# Pin_Expansion.net
KiCad netlist of a schematic drawn in Altium Designer
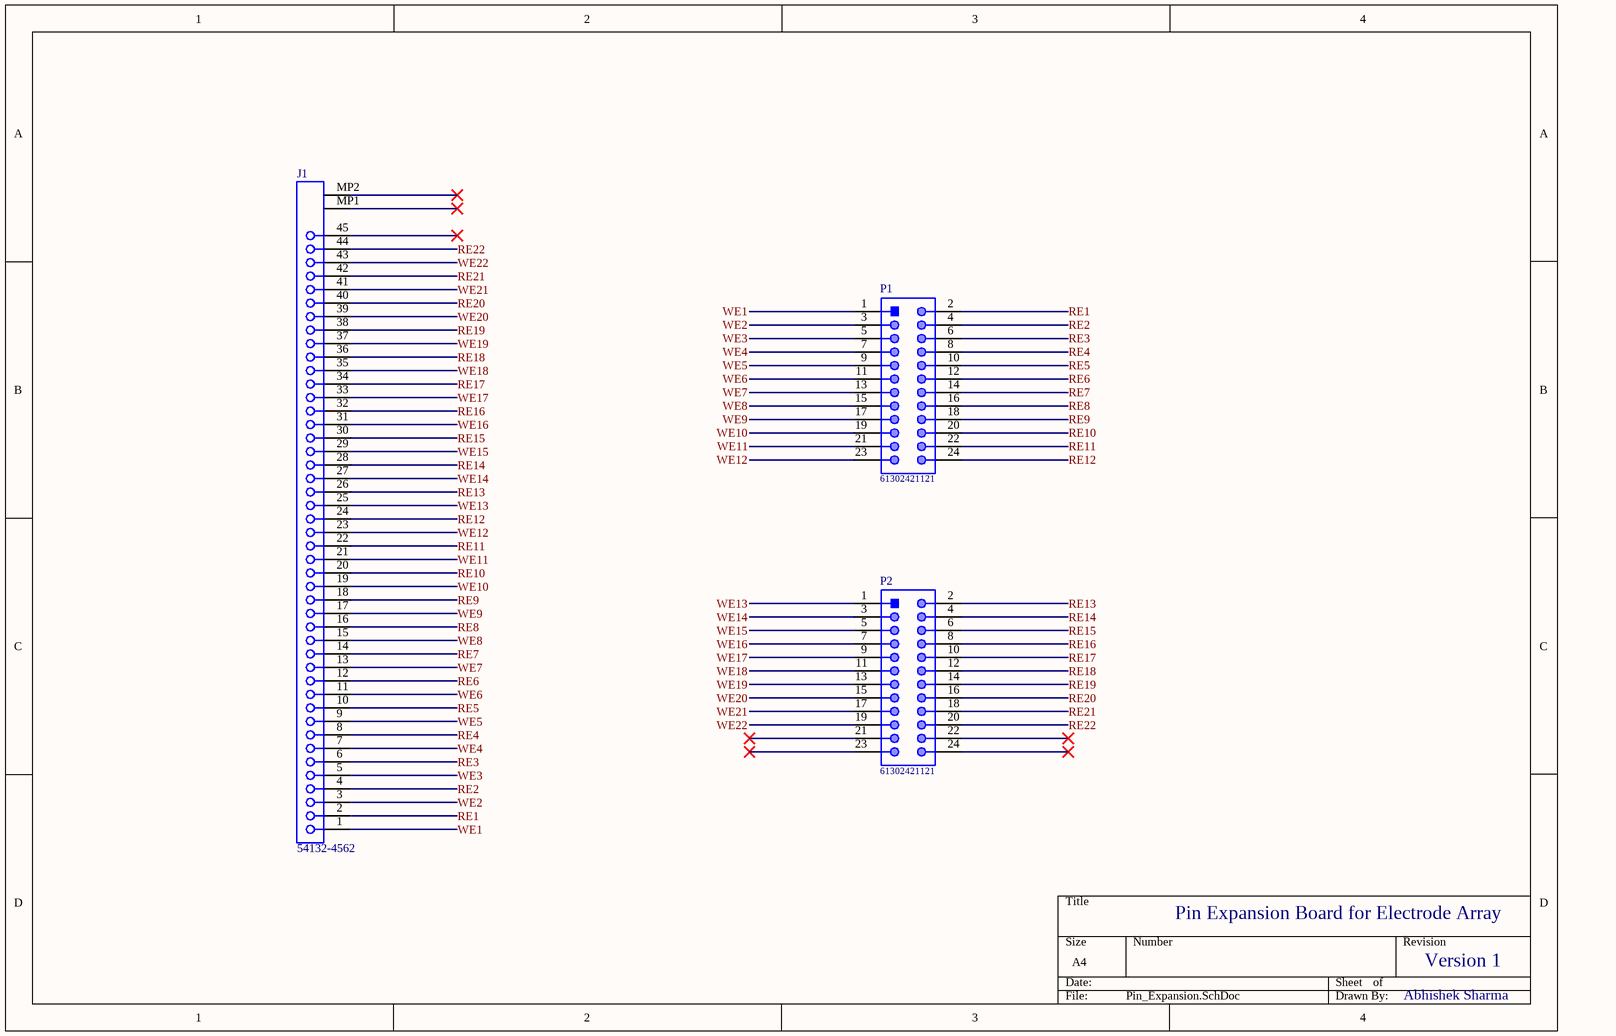
[diagram p0: Pin_Expansion.SchDoc]

(export (version "E")
  (design (tool "Eeschema 10.0.6"))
  (components
    (comp (ref "J1")
      (value "54132-4562")
      (footprint "MOLX-54132-4562")
      (fields (field (name "MANUFACTURER") "Molex"))
      (libsource (lib "Altium Content Vault") (part "MOLX-54132-4562"))
    )
    (comp (ref "P1")
      (value "61302421121")
      (footprint "61302421121")
      (description "THT Vertical Pin Header WR-PHD, Pitch 2.54 mm, Dual Row, 24 pins")
      (fields (field (name "MANUFACTURER") "Wurth Elektronik") (field (name "PUBLISHER") "WurthElektronik"))
      (libsource (lib "Altium Content Vault") (part "WE-CN-2P-M-R24"))
    )
    (comp (ref "P2")
      (value "61302421121")
      (footprint "61302421121")
      (description "THT Vertical Pin Header WR-PHD, Pitch 2.54 mm, Dual Row, 24 pins")
      (fields (field (name "MANUFACTURER") "Wurth Elektronik") (field (name "PUBLISHER") "WurthElektronik"))
      (libsource (lib "Altium Content Vault") (part "WE-CN-2P-M-R24"))
    )
  )
  (nets
    (net (code "1") (name "/RE1") (class "Default")
      (node (ref "J1") (pin "2") (pinfunction "2_2") (pintype "passive"))
      (node (ref "P1") (pin "2") (pinfunction "2_2") (pintype "passive"))
    )
    (net (code "2") (name "/RE2") (class "Default")
      (node (ref "J1") (pin "4") (pinfunction "4_4") (pintype "passive"))
      (node (ref "P1") (pin "4") (pinfunction "4_4") (pintype "passive"))
    )
    (net (code "3") (name "/RE3") (class "Default")
      (node (ref "J1") (pin "6") (pinfunction "6_6") (pintype "passive"))
      (node (ref "P1") (pin "6") (pinfunction "6_6") (pintype "passive"))
    )
    (net (code "4") (name "/RE4") (class "Default")
      (node (ref "J1") (pin "8") (pinfunction "8_8") (pintype "passive"))
      (node (ref "P1") (pin "8") (pinfunction "8_8") (pintype "passive"))
    )
    (net (code "5") (name "/RE5") (class "Default")
      (node (ref "J1") (pin "10") (pinfunction "10_10") (pintype "passive"))
      (node (ref "P1") (pin "10") (pinfunction "10_10") (pintype "passive"))
    )
    (net (code "6") (name "/RE6") (class "Default")
      (node (ref "J1") (pin "12") (pinfunction "12_12") (pintype "passive"))
      (node (ref "P1") (pin "12") (pinfunction "12_12") (pintype "passive"))
    )
    (net (code "7") (name "/RE7") (class "Default")
      (node (ref "J1") (pin "14") (pinfunction "14_14") (pintype "passive"))
      (node (ref "P1") (pin "14") (pinfunction "14_14") (pintype "passive"))
    )
    (net (code "8") (name "/RE8") (class "Default")
      (node (ref "J1") (pin "16") (pinfunction "16_16") (pintype "passive"))
      (node (ref "P1") (pin "16") (pinfunction "16_16") (pintype "passive"))
    )
    (net (code "9") (name "/RE9") (class "Default")
      (node (ref "J1") (pin "18") (pinfunction "18_18") (pintype "passive"))
      (node (ref "P1") (pin "18") (pinfunction "18_18") (pintype "passive"))
    )
    (net (code "10") (name "/RE10") (class "Default")
      (node (ref "J1") (pin "20") (pinfunction "20_20") (pintype "passive"))
      (node (ref "P1") (pin "20") (pinfunction "20_20") (pintype "passive"))
    )
    (net (code "11") (name "/RE11") (class "Default")
      (node (ref "J1") (pin "22") (pinfunction "22_22") (pintype "passive"))
      (node (ref "P1") (pin "22") (pinfunction "22_22") (pintype "passive"))
    )
    (net (code "12") (name "/RE12") (class "Default")
      (node (ref "J1") (pin "24") (pinfunction "24_24") (pintype "passive"))
      (node (ref "P1") (pin "24") (pinfunction "24_24") (pintype "passive"))
    )
    (net (code "13") (name "/RE13") (class "Default")
      (node (ref "J1") (pin "26") (pinfunction "26_26") (pintype "passive"))
      (node (ref "P2") (pin "2") (pinfunction "2_2") (pintype "passive"))
    )
    (net (code "14") (name "/RE14") (class "Default")
      (node (ref "J1") (pin "28") (pinfunction "28_28") (pintype "passive"))
      (node (ref "P2") (pin "4") (pinfunction "4_4") (pintype "passive"))
    )
    (net (code "15") (name "/RE15") (class "Default")
      (node (ref "J1") (pin "30") (pinfunction "30_30") (pintype "passive"))
      (node (ref "P2") (pin "6") (pinfunction "6_6") (pintype "passive"))
    )
    (net (code "16") (name "/RE16") (class "Default")
      (node (ref "J1") (pin "32") (pinfunction "32_32") (pintype "passive"))
      (node (ref "P2") (pin "8") (pinfunction "8_8") (pintype "passive"))
    )
    (net (code "17") (name "/RE17") (class "Default")
      (node (ref "J1") (pin "34") (pinfunction "34_34") (pintype "passive"))
      (node (ref "P2") (pin "10") (pinfunction "10_10") (pintype "passive"))
    )
    (net (code "18") (name "/RE18") (class "Default")
      (node (ref "J1") (pin "36") (pinfunction "36_36") (pintype "passive"))
      (node (ref "P2") (pin "12") (pinfunction "12_12") (pintype "passive"))
    )
    (net (code "19") (name "/RE19") (class "Default")
      (node (ref "J1") (pin "38") (pinfunction "38_38") (pintype "passive"))
      (node (ref "P2") (pin "14") (pinfunction "14_14") (pintype "passive"))
    )
    (net (code "20") (name "/RE20") (class "Default")
      (node (ref "J1") (pin "40") (pinfunction "40_40") (pintype "passive"))
      (node (ref "P2") (pin "16") (pinfunction "16_16") (pintype "passive"))
    )
    (net (code "21") (name "/RE21") (class "Default")
      (node (ref "J1") (pin "42") (pinfunction "42_42") (pintype "passive"))
      (node (ref "P2") (pin "18") (pinfunction "18_18") (pintype "passive"))
    )
    (net (code "22") (name "/RE22") (class "Default")
      (node (ref "J1") (pin "44") (pinfunction "44_44") (pintype "passive"))
      (node (ref "P2") (pin "20") (pinfunction "20_20") (pintype "passive"))
    )
    (net (code "23") (name "/WE1") (class "Default")
      (node (ref "J1") (pin "1") (pinfunction "1_1") (pintype "passive"))
      (node (ref "P1") (pin "1") (pinfunction "1_1") (pintype "passive"))
    )
    (net (code "24") (name "/WE2") (class "Default")
      (node (ref "J1") (pin "3") (pinfunction "3_3") (pintype "passive"))
      (node (ref "P1") (pin "3") (pinfunction "3_3") (pintype "passive"))
    )
    (net (code "25") (name "/WE3") (class "Default")
      (node (ref "J1") (pin "5") (pinfunction "5_5") (pintype "passive"))
      (node (ref "P1") (pin "5") (pinfunction "5_5") (pintype "passive"))
    )
    (net (code "26") (name "/WE4") (class "Default")
      (node (ref "J1") (pin "7") (pinfunction "7_7") (pintype "passive"))
      (node (ref "P1") (pin "7") (pinfunction "7_7") (pintype "passive"))
    )
    (net (code "27") (name "/WE5") (class "Default")
      (node (ref "J1") (pin "9") (pinfunction "9_9") (pintype "passive"))
      (node (ref "P1") (pin "9") (pinfunction "9_9") (pintype "passive"))
    )
    (net (code "28") (name "/WE6") (class "Default")
      (node (ref "J1") (pin "11") (pinfunction "11_11") (pintype "passive"))
      (node (ref "P1") (pin "11") (pinfunction "11_11") (pintype "passive"))
    )
    (net (code "29") (name "/WE7") (class "Default")
      (node (ref "J1") (pin "13") (pinfunction "13_13") (pintype "passive"))
      (node (ref "P1") (pin "13") (pinfunction "13_13") (pintype "passive"))
    )
    (net (code "30") (name "/WE8") (class "Default")
      (node (ref "J1") (pin "15") (pinfunction "15_15") (pintype "passive"))
      (node (ref "P1") (pin "15") (pinfunction "15_15") (pintype "passive"))
    )
    (net (code "31") (name "/WE9") (class "Default")
      (node (ref "J1") (pin "17") (pinfunction "17_17") (pintype "passive"))
      (node (ref "P1") (pin "17") (pinfunction "17_17") (pintype "passive"))
    )
    (net (code "32") (name "/WE10") (class "Default")
      (node (ref "J1") (pin "19") (pinfunction "19_19") (pintype "passive"))
      (node (ref "P1") (pin "19") (pinfunction "19_19") (pintype "passive"))
    )
    (net (code "33") (name "/WE11") (class "Default")
      (node (ref "J1") (pin "21") (pinfunction "21_21") (pintype "passive"))
      (node (ref "P1") (pin "21") (pinfunction "21_21") (pintype "passive"))
    )
    (net (code "34") (name "/WE12") (class "Default")
      (node (ref "J1") (pin "23") (pinfunction "23_23") (pintype "passive"))
      (node (ref "P1") (pin "23") (pinfunction "23_23") (pintype "passive"))
    )
    (net (code "35") (name "/WE13") (class "Default")
      (node (ref "J1") (pin "25") (pinfunction "25_25") (pintype "passive"))
      (node (ref "P2") (pin "1") (pinfunction "1_1") (pintype "passive"))
    )
    (net (code "36") (name "/WE14") (class "Default")
      (node (ref "J1") (pin "27") (pinfunction "27_27") (pintype "passive"))
      (node (ref "P2") (pin "3") (pinfunction "3_3") (pintype "passive"))
    )
    (net (code "37") (name "/WE15") (class "Default")
      (node (ref "J1") (pin "29") (pinfunction "29_29") (pintype "passive"))
      (node (ref "P2") (pin "5") (pinfunction "5_5") (pintype "passive"))
    )
    (net (code "38") (name "/WE16") (class "Default")
      (node (ref "J1") (pin "31") (pinfunction "31_31") (pintype "passive"))
      (node (ref "P2") (pin "7") (pinfunction "7_7") (pintype "passive"))
    )
    (net (code "39") (name "/WE17") (class "Default")
      (node (ref "J1") (pin "33") (pinfunction "33_33") (pintype "passive"))
      (node (ref "P2") (pin "9") (pinfunction "9_9") (pintype "passive"))
    )
    (net (code "40") (name "/WE18") (class "Default")
      (node (ref "J1") (pin "35") (pinfunction "35_35") (pintype "passive"))
      (node (ref "P2") (pin "11") (pinfunction "11_11") (pintype "passive"))
    )
    (net (code "41") (name "/WE19") (class "Default")
      (node (ref "J1") (pin "37") (pinfunction "37_37") (pintype "passive"))
      (node (ref "P2") (pin "13") (pinfunction "13_13") (pintype "passive"))
    )
    (net (code "42") (name "/WE20") (class "Default")
      (node (ref "J1") (pin "39") (pinfunction "39_39") (pintype "passive"))
      (node (ref "P2") (pin "15") (pinfunction "15_15") (pintype "passive"))
    )
    (net (code "43") (name "/WE21") (class "Default")
      (node (ref "J1") (pin "41") (pinfunction "41_41") (pintype "passive"))
      (node (ref "P2") (pin "17") (pinfunction "17_17") (pintype "passive"))
    )
    (net (code "44") (name "/WE22") (class "Default")
      (node (ref "J1") (pin "43") (pinfunction "43_43") (pintype "passive"))
      (node (ref "P2") (pin "19") (pinfunction "19_19") (pintype "passive"))
    )
    (net (code "45") (name "unconnected-(J1-Pad45)") (class "Default")
      (node (ref "J1") (pin "45") (pinfunction "45_45") (pintype "passive+no_connect"))
    )
    (net (code "46") (name "unconnected-(J1-PadMP1)") (class "Default")
      (node (ref "J1") (pin "MP1") (pinfunction "MP1_MP1") (pintype "passive+no_connect"))
    )
    (net (code "47") (name "unconnected-(J1-PadMP2)") (class "Default")
      (node (ref "J1") (pin "MP2") (pinfunction "MP2_MP2") (pintype "passive+no_connect"))
    )
    (net (code "48") (name "unconnected-(P2-Pad21)") (class "Default")
      (node (ref "P2") (pin "21") (pinfunction "21_21") (pintype "passive+no_connect"))
    )
    (net (code "49") (name "unconnected-(P2-Pad22)") (class "Default")
      (node (ref "P2") (pin "22") (pinfunction "22_22") (pintype "passive+no_connect"))
    )
    (net (code "50") (name "unconnected-(P2-Pad23)") (class "Default")
      (node (ref "P2") (pin "23") (pinfunction "23_23") (pintype "passive+no_connect"))
    )
    (net (code "51") (name "unconnected-(P2-Pad24)") (class "Default")
      (node (ref "P2") (pin "24") (pinfunction "24_24") (pintype "passive+no_connect"))
    )
  )
)
